# design.net
KiCad netlist of a schematic drawn in Altium Designer
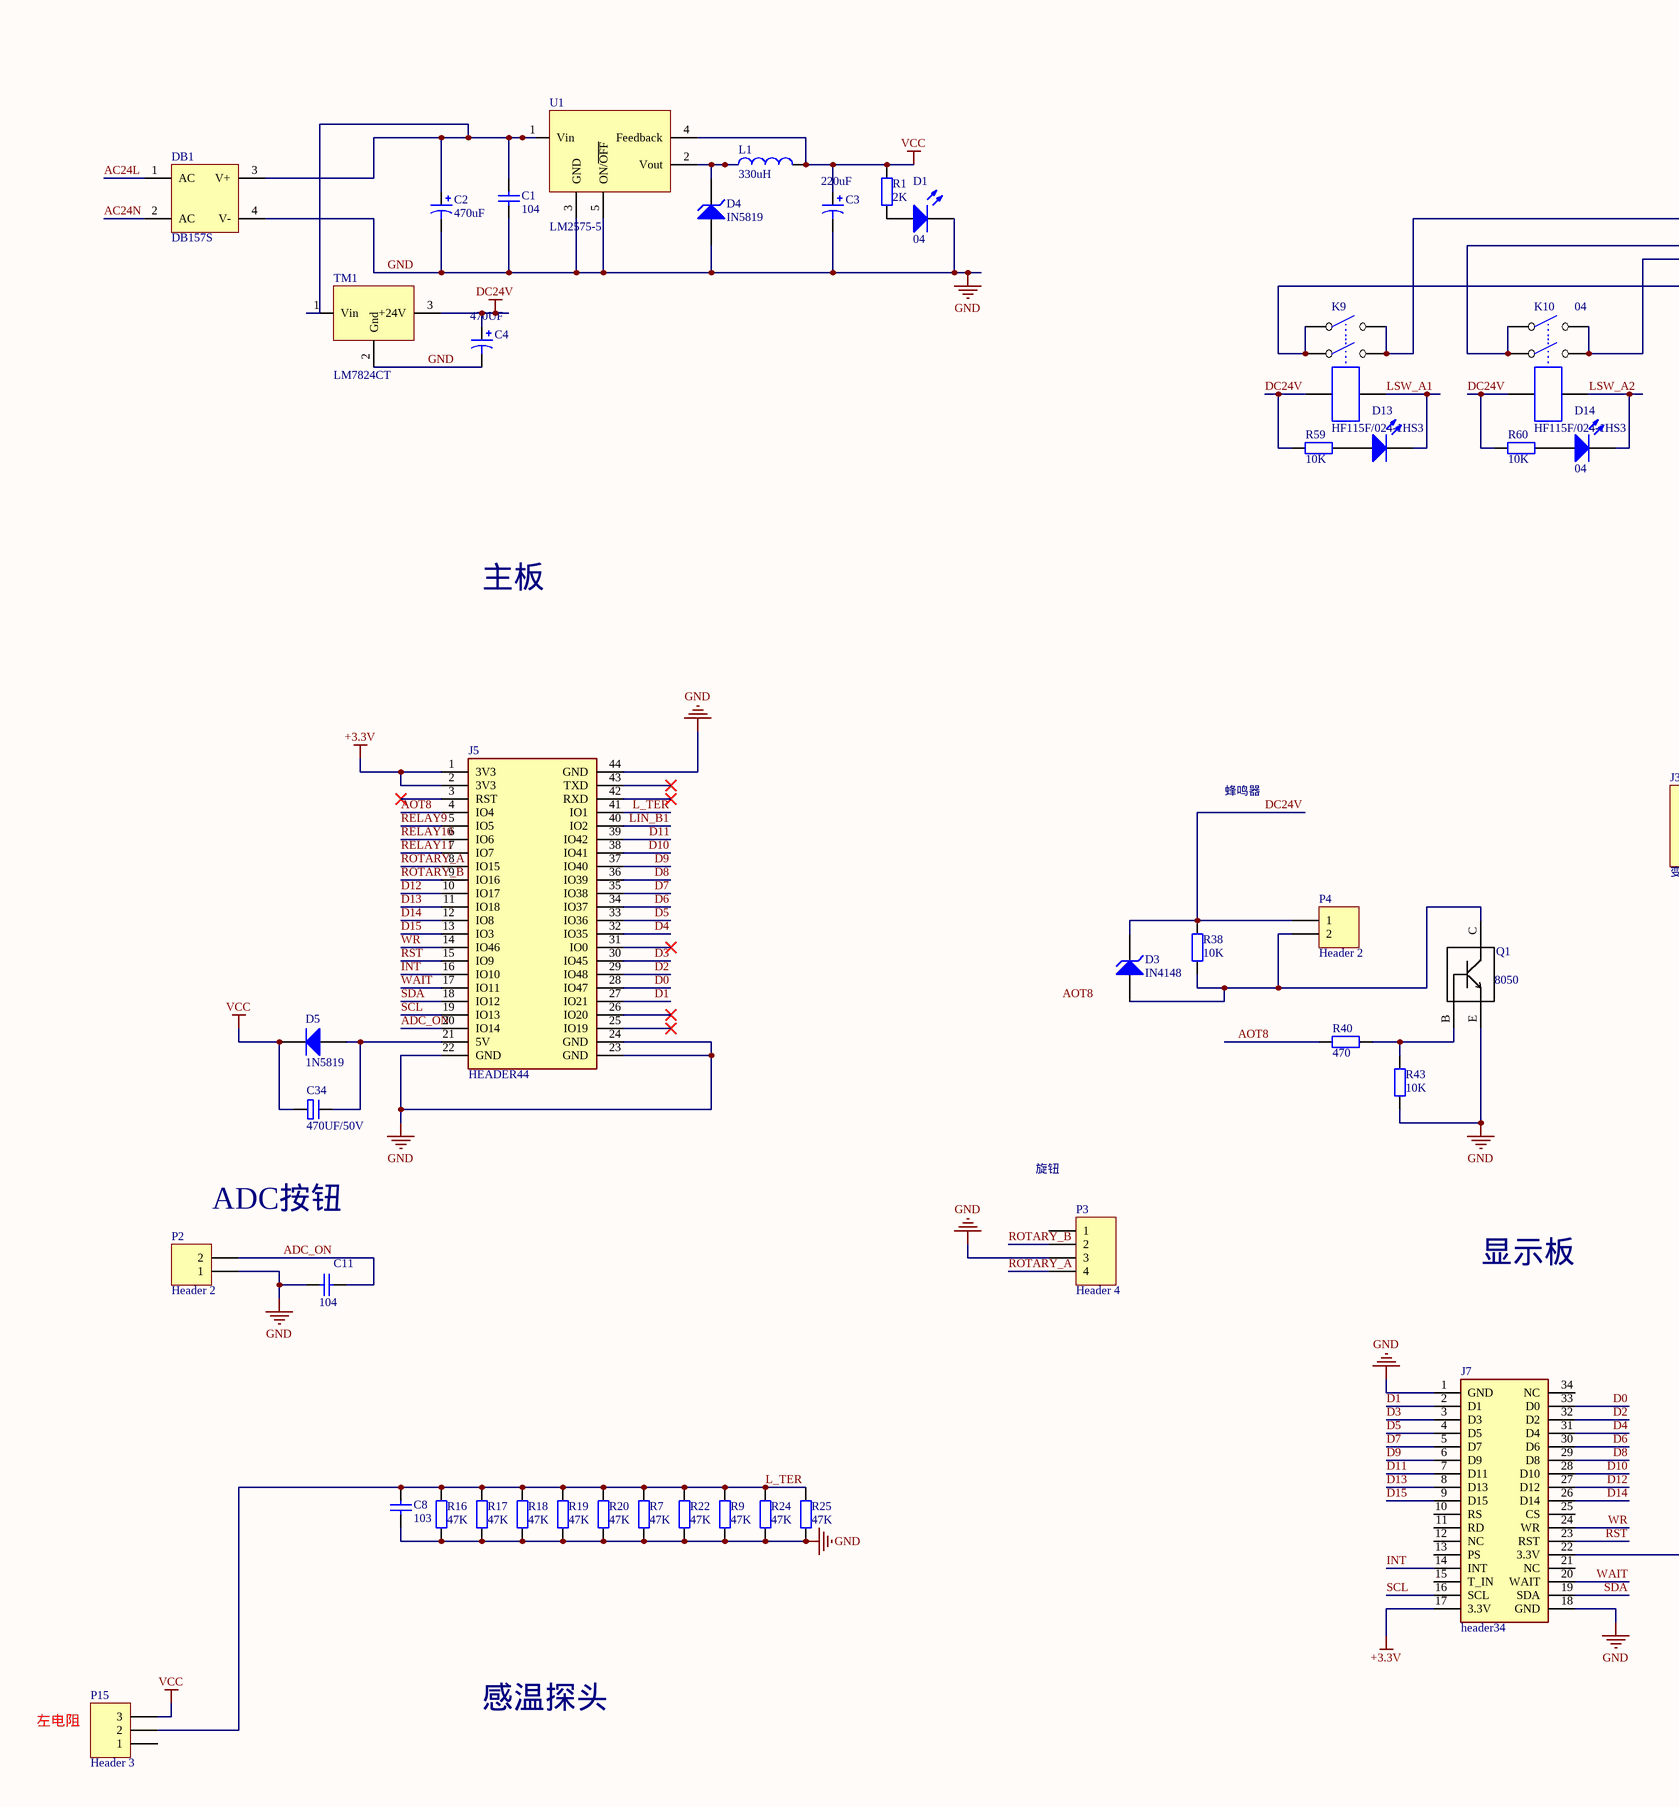
[diagram p0: 下程序新版.SchDoc, left]
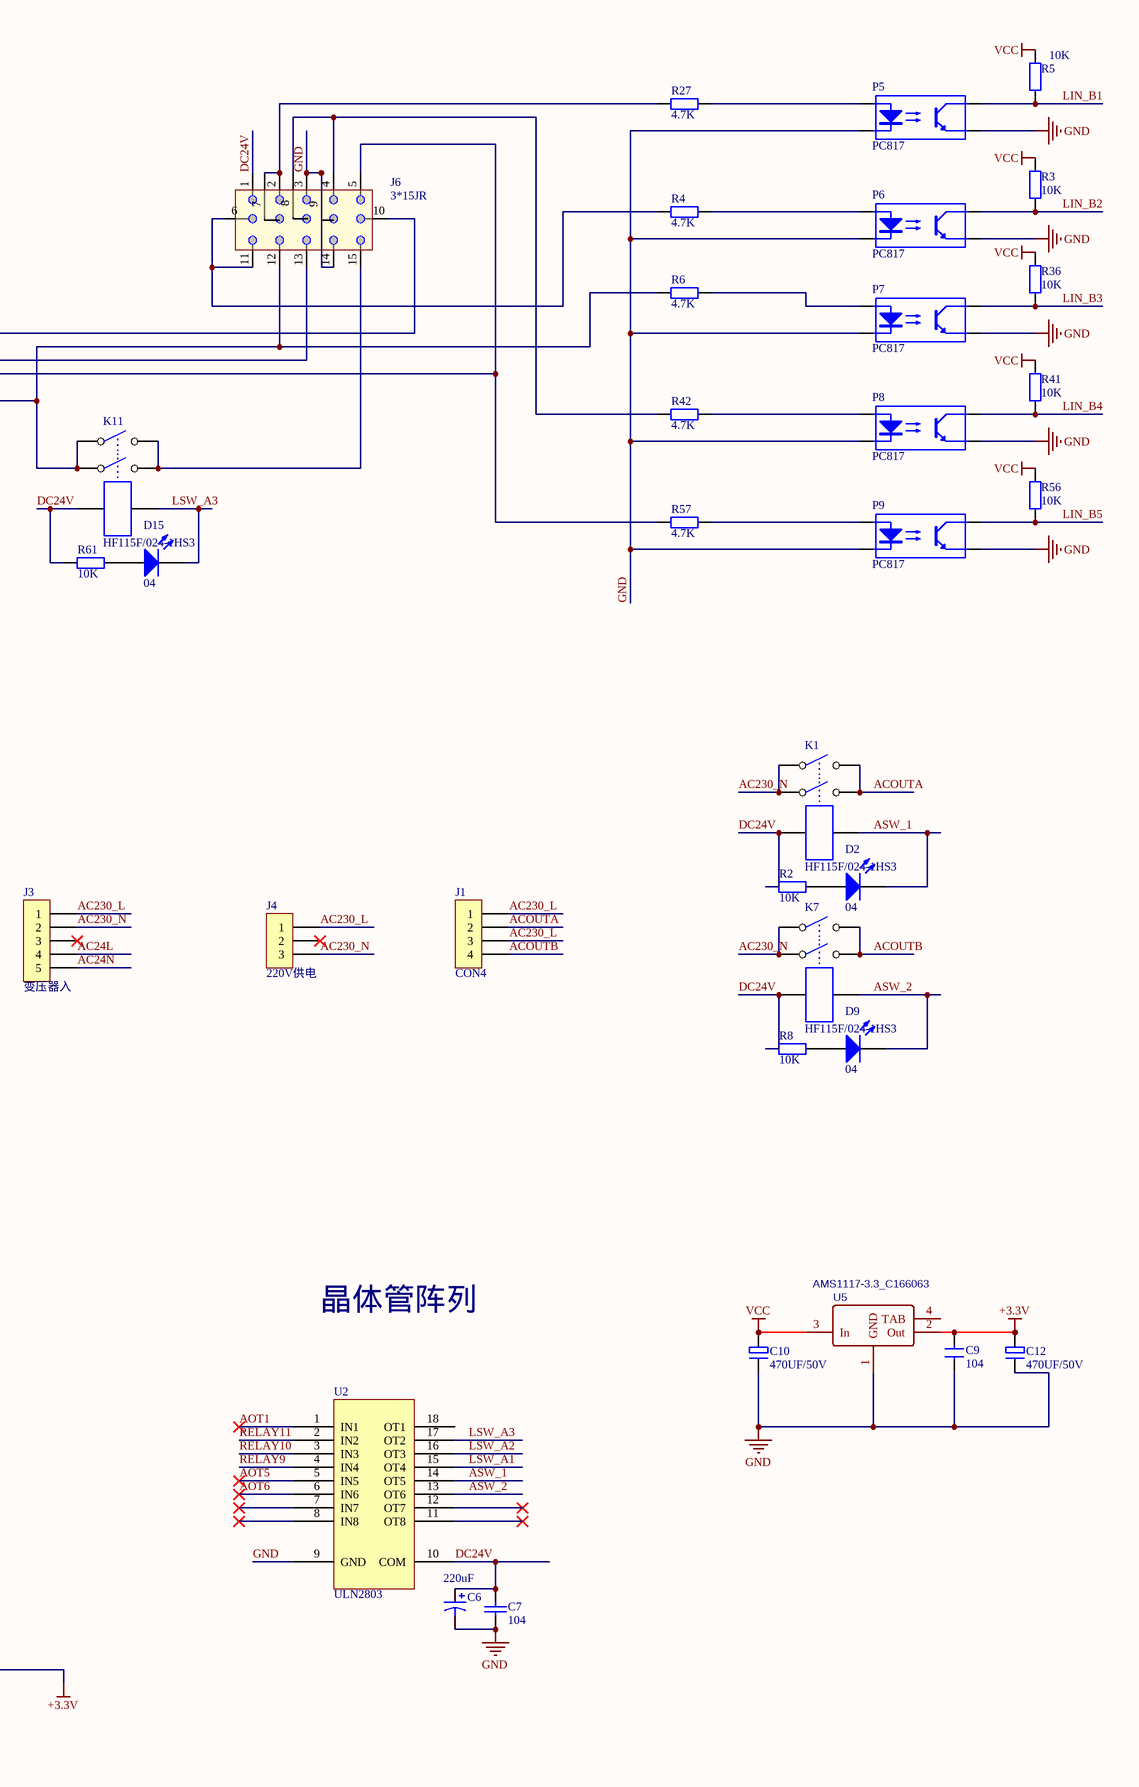
[diagram p1: 下程序新版.SchDoc, right]

(export (version "E")
  (design (tool "Eeschema 10.0.6"))
  (components
    (comp (ref "C1")
      (value "104")
      (footprint "PcbLib1:0805")
      (description "Capacitor")
      (fields (field (name "PUBLISHER") "Altium Limited"))
      (libsource (lib "Miscellaneous Devices") (part "Cap"))
    )
    (comp (ref "C2")
      (value "470uF")
      (footprint "PcbLib1:CD9")
      (description "Polarized Capacitor (Radial)")
      (fields (field (name "Comment") "470UF/50V") (field (name "PUBLISHER") "Altium Limited"))
      (libsource (lib "Miscellaneous Devices") (part "Cap Pol1"))
    )
    (comp (ref "C3")
      (value "220uF")
      (footprint "PcbLib1:CD9")
      (description "Polarized Capacitor (Radial)")
      (fields (field (name "PUBLISHER") "Altium Limited"))
      (libsource (lib "Miscellaneous Devices") (part "Cap Pol1"))
    )
    (comp (ref "C4")
      (value "470UF")
      (footprint "PcbLib1:CD9")
      (description "Polarized Capacitor (Radial)")
      (fields (field (name "PUBLISHER") "Altium Limited"))
      (libsource (lib "Miscellaneous Devices") (part "Cap Pol1"))
    )
    (comp (ref "C6")
      (value "220uF")
      (footprint "PcbLib1:CD9")
      (description "Polarized Capacitor (Radial)")
      (fields (field (name "PUBLISHER") "Altium Limited"))
      (libsource (lib "Miscellaneous Devices") (part "Cap Pol1"))
    )
    (comp (ref "C7")
      (value "104")
      (footprint "PcbLib1:0805")
      (description "Capacitor")
      (fields (field (name "PUBLISHER") "Altium Limited"))
      (libsource (lib "Miscellaneous Devices") (part "Cap"))
    )
    (comp (ref "C8")
      (value "103")
      (footprint "PcbLib1:0805")
      (description "Capacitor")
      (fields (field (name "PUBLISHER") "Altium Limited"))
      (libsource (lib "Miscellaneous Devices") (part "Cap"))
    )
    (comp (ref "C9") (value "104") (footprint "PcbLib1:0805") (libsource (lib "Altium") (part "CAP")))
    (comp (ref "C10") (value "470UF/50V") (footprint "PcbLib1:CD9") (libsource (lib "Altium") (part "ECAP")))
    (comp (ref "C11")
      (value "104")
      (footprint "PcbLib1:0805")
      (description "Capacitor")
      (fields (field (name "PUBLISHER") "Altium Limited"))
      (libsource (lib "Miscellaneous Devices") (part "Cap"))
    )
    (comp (ref "C12") (value "470UF/50V") (footprint "PcbLib1:CD9") (libsource (lib "Altium") (part "ECAP")))
    (comp (ref "C34") (value "470UF/50V") (footprint "PcbLib1:CD9") (libsource (lib "Altium") (part "ECAP")))
    (comp (ref "D1")
      (value "04")
      (footprint "PcbLib1:LED-T")
      (description "Typical INFRARED GaAs LED")
      (fields (field (name "PUBLISHER") "Altium Limited"))
      (libsource (lib "Miscellaneous Devices") (part "LED0"))
    )
    (comp (ref "D2")
      (value "04")
      (footprint "PcbLib1:LED-T")
      (description "Typical INFRARED GaAs LED")
      (fields (field (name "PUBLISHER") "Altium Limited"))
      (libsource (lib "Miscellaneous Devices") (part "LED0"))
    )
    (comp (ref "D3")
      (value "IN4148")
      (footprint "PcbLib1:DO-214AC")
      (description "Zener Diode")
      (fields (field (name "PUBLISHER") "Altium Limited"))
      (libsource (lib "Miscellaneous Devices") (part "D Zener"))
    )
    (comp (ref "D4")
      (value "IN5819")
      (footprint "PcbLib1:DO-214AC")
      (description "Zener Diode")
      (fields (field (name "PUBLISHER") "Altium Limited"))
      (libsource (lib "Miscellaneous Devices") (part "D Zener"))
    )
    (comp (ref "D5")
      (value "1N5819")
      (footprint "PcbLib1:DO-214AC")
      (description "High Conductance Fast Diode")
      (fields (field (name "PUBLISHER") "Altium Limited"))
      (libsource (lib "Drive") (part "Diode 1N4148"))
    )
    (comp (ref "D9")
      (value "04")
      (footprint "PcbLib1:LED-T")
      (description "Typical INFRARED GaAs LED")
      (fields (field (name "PUBLISHER") "Altium Limited"))
      (libsource (lib "Miscellaneous Devices") (part "LED0"))
    )
    (comp (ref "D13")
      (value "04")
      (footprint "PcbLib1:LED-T")
      (description "Typical INFRARED GaAs LED")
      (fields (field (name "PUBLISHER") "Altium Limited"))
      (libsource (lib "Miscellaneous Devices") (part "LED0"))
    )
    (comp (ref "D14")
      (value "04")
      (footprint "PcbLib1:LED-T")
      (description "Typical INFRARED GaAs LED")
      (fields (field (name "PUBLISHER") "Altium Limited"))
      (libsource (lib "Miscellaneous Devices") (part "LED0"))
    )
    (comp (ref "D15")
      (value "04")
      (footprint "PcbLib1:LED-T")
      (description "Typical INFRARED GaAs LED")
      (fields (field (name "PUBLISHER") "Altium Limited"))
      (libsource (lib "Miscellaneous Devices") (part "LED0"))
    )
    (comp (ref "DB1")
      (value "DB157S")
      (footprint "PcbLib1:LC-GBU")
      (libsource (lib "常用元件库") (part "BRIDGE2"))
    )
    (comp (ref "J1")
      (value "CON4")
      (footprint "PcbLib1:4PIN-6.3")
      (description "Connector")
      (libsource (lib "Miscellaneous Devices") (part "CON4"))
    )
    (comp (ref "J3")
      (value "变压器入")
      (footprint "PcbLib1:5PIN-6.3")
      (description "Connector")
      (libsource (lib "Miscellaneous Devices") (part "CON5"))
    )
    (comp (ref "J4")
      (value "220V供电")
      (footprint "PcbLib1:3PIN-6.3")
      (description "Connector")
      (libsource (lib "Miscellaneous Devices") (part "CON3"))
    )
    (comp (ref "J5")
      (value "HEADER44")
      (footprint "SAMTEC_HTSW-110-24-TM-D")
      (fields (field (name "MF") "Samtec") (field (name "MP") "HTSW11024TMD"))
      (libsource (lib "Drive") (part "HEADER44"))
    )
    (comp (ref "J6")
      (value "3*15JR")
      (footprint "PcbLib1:3*5PIN-6.3")
      (libsource (lib "Schlib1") (part "Component_1"))
    )
    (comp (ref "J7")
      (value "header34")
      (footprint "SAMTEC_HTSW-110-24-TM-D")
      (fields (field (name "MF") "Samtec") (field (name "MP") "HTSW11024TMD"))
      (libsource (lib "Drive") (part "header34"))
    )
    (comp (ref "K1")
      (value "HF115F/024-1HS3")
      (footprint "PcbLib1:HF115FA")
      (libsource (lib "Miscellaneous Devices") (part "RELAY-DPST"))
    )
    (comp (ref "K7")
      (value "HF115F/024-1HS3")
      (footprint "PcbLib1:HF115FA")
      (libsource (lib "Miscellaneous Devices") (part "RELAY-DPST"))
    )
    (comp (ref "K9")
      (value "HF115F/024-1HS3")
      (footprint "PcbLib1:HF115FA")
      (libsource (lib "Miscellaneous Devices") (part "RELAY-DPST"))
    )
    (comp (ref "K10")
      (value "HF115F/024-1HS3")
      (footprint "PcbLib1:HF115FA")
      (libsource (lib "Miscellaneous Devices") (part "RELAY-DPST"))
    )
    (comp (ref "K11")
      (value "HF115F/024-1HS3")
      (footprint "PcbLib1:HF115FA")
      (libsource (lib "Miscellaneous Devices") (part "RELAY-DPST"))
    )
    (comp (ref "L1")
      (value "330uH")
      (footprint "PcbLib1:SMD331")
      (description "Inductor")
      (fields (field (name "PUBLISHER") "Altium Limited"))
      (libsource (lib "Miscellaneous Devices") (part "Inductor"))
    )
    (comp (ref "P2")
      (value "Header 2")
      (footprint "PcbLib1:2PIN 3.96")
      (description "Header, 2-Pin")
      (fields (field (name "PUBLISHER") "Altium Limited"))
      (libsource (lib "Drive") (part "Header 2"))
    )
    (comp (ref "P3")
      (value "Header 4")
      (footprint "PcbLib1:4PIN 2.54")
      (description "Header, 4-Pin")
      (fields (field (name "PUBLISHER") "Altium Limited"))
      (libsource (lib "Drive") (part "Header 4"))
    )
    (comp (ref "P4")
      (value "Header 2")
      (footprint "PcbLib1:2PIN 3.96")
      (description "Header, 2-Pin")
      (fields (field (name "PUBLISHER") "Altium Limited"))
      (libsource (lib "Miscellaneous Connectors") (part "Header 2"))
    )
    (comp (ref "P5") (value "PC817") (footprint "PcbLib1:LC-SMD-4") (libsource (lib "常用元件库") (part "P521")))
    (comp (ref "P6") (value "PC817") (footprint "PcbLib1:LC-SMD-4") (libsource (lib "常用元件库") (part "P521")))
    (comp (ref "P7") (value "PC817") (footprint "PcbLib1:LC-SMD-4") (libsource (lib "常用元件库") (part "P521")))
    (comp (ref "P8") (value "PC817") (footprint "PcbLib1:LC-SMD-4") (libsource (lib "常用元件库") (part "P521")))
    (comp (ref "P9") (value "PC817") (footprint "PcbLib1:LC-SMD-4") (libsource (lib "常用元件库") (part "P521")))
    (comp (ref "P15")
      (value "Header 3")
      (footprint "PcbLib1:3PIN 3.96")
      (description "Header, 3-Pin")
      (fields (field (name "PUBLISHER") "Altium Limited"))
      (libsource (lib "Miscellaneous Connectors") (part "Header 3"))
    )
    (comp (ref "Q1")
      (value "8050")
      (footprint "PcbLib1:SOT-23 - duplicate")
      (libsource (lib "Schlib1") (part "BC817-8050"))
    )
    (comp (ref "R1")
      (value "2K")
      (footprint "PcbLib1:0805")
      (description "Resistor")
      (fields (field (name "PUBLISHER") "Altium Limited"))
      (libsource (lib "Miscellaneous Devices") (part "Res2"))
    )
    (comp (ref "R2")
      (value "10K")
      (footprint "PcbLib1:0805")
      (description "Resistor")
      (fields (field (name "Comment") "10k") (field (name "PUBLISHER") "Altium Limited"))
      (libsource (lib "") (part "Res2_2"))
    )
    (comp (ref "R3")
      (value "10K")
      (footprint "PcbLib1:0805")
      (description "Resistor")
      (fields (field (name "Comment") "10k") (field (name "PUBLISHER") "Altium Limited"))
      (libsource (lib "Miscellaneous Devices") (part "Res2"))
    )
    (comp (ref "R4")
      (value "4.7K")
      (footprint "PcbLib1:0805")
      (description "Resistor")
      (fields (field (name "PUBLISHER") "Altium Limited"))
      (libsource (lib "") (part "Res2_1"))
    )
    (comp (ref "R5")
      (value "10K")
      (footprint "PcbLib1:0805")
      (description "Resistor")
      (fields (field (name "Comment") "10k") (field (name "PUBLISHER") "Altium Limited"))
      (libsource (lib "Miscellaneous Devices") (part "Res2"))
    )
    (comp (ref "R6")
      (value "4.7K")
      (footprint "PcbLib1:0805")
      (description "Resistor")
      (fields (field (name "PUBLISHER") "Altium Limited"))
      (libsource (lib "") (part "Res2_1"))
    )
    (comp (ref "R7")
      (value "47K")
      (footprint "PcbLib1:0805")
      (description "Resistor")
      (fields (field (name "PUBLISHER") "Altium Limited"))
      (libsource (lib "Miscellaneous Devices") (part "Res2"))
    )
    (comp (ref "R8")
      (value "10K")
      (footprint "PcbLib1:0805")
      (description "Resistor")
      (fields (field (name "Comment") "10k") (field (name "PUBLISHER") "Altium Limited"))
      (libsource (lib "") (part "Res2_2"))
    )
    (comp (ref "R9")
      (value "47K")
      (footprint "PcbLib1:0805")
      (description "Resistor")
      (fields (field (name "PUBLISHER") "Altium Limited"))
      (libsource (lib "Miscellaneous Devices") (part "Res2"))
    )
    (comp (ref "R16")
      (value "47K")
      (footprint "PcbLib1:0805")
      (description "Resistor")
      (fields (field (name "PUBLISHER") "Altium Limited"))
      (libsource (lib "Miscellaneous Devices") (part "Res2"))
    )
    (comp (ref "R17")
      (value "47K")
      (footprint "PcbLib1:0805")
      (description "Resistor")
      (fields (field (name "PUBLISHER") "Altium Limited"))
      (libsource (lib "Miscellaneous Devices") (part "Res2"))
    )
    (comp (ref "R18")
      (value "47K")
      (footprint "PcbLib1:0805")
      (description "Resistor")
      (fields (field (name "PUBLISHER") "Altium Limited"))
      (libsource (lib "Miscellaneous Devices") (part "Res2"))
    )
    (comp (ref "R19")
      (value "47K")
      (footprint "PcbLib1:0805")
      (description "Resistor")
      (fields (field (name "PUBLISHER") "Altium Limited"))
      (libsource (lib "Miscellaneous Devices") (part "Res2"))
    )
    (comp (ref "R20")
      (value "47K")
      (footprint "PcbLib1:0805")
      (description "Resistor")
      (fields (field (name "PUBLISHER") "Altium Limited"))
      (libsource (lib "Miscellaneous Devices") (part "Res2"))
    )
    (comp (ref "R22")
      (value "47K")
      (footprint "PcbLib1:0805")
      (description "Resistor")
      (fields (field (name "PUBLISHER") "Altium Limited"))
      (libsource (lib "Miscellaneous Devices") (part "Res2"))
    )
    (comp (ref "R24")
      (value "47K")
      (footprint "PcbLib1:0805")
      (description "Resistor")
      (fields (field (name "PUBLISHER") "Altium Limited"))
      (libsource (lib "Miscellaneous Devices") (part "Res2"))
    )
    (comp (ref "R25")
      (value "47K")
      (footprint "PcbLib1:0805")
      (description "Resistor")
      (fields (field (name "PUBLISHER") "Altium Limited"))
      (libsource (lib "Miscellaneous Devices") (part "Res2"))
    )
    (comp (ref "R27")
      (value "4.7K")
      (footprint "PcbLib1:0805")
      (description "Resistor")
      (fields (field (name "PUBLISHER") "Altium Limited"))
      (libsource (lib "") (part "Res2_1"))
    )
    (comp (ref "R36")
      (value "10K")
      (footprint "PcbLib1:0805")
      (description "Resistor")
      (fields (field (name "Comment") "10k") (field (name "PUBLISHER") "Altium Limited"))
      (libsource (lib "Miscellaneous Devices") (part "Res2"))
    )
    (comp (ref "R38")
      (value "10K")
      (footprint "0805")
      (description "Resistor")
      (fields (field (name "PUBLISHER") "Altium Limited"))
      (libsource (lib "Miscellaneous Devices") (part "Res2"))
    )
    (comp (ref "R40")
      (value "470")
      (footprint "0805")
      (description "Resistor")
      (fields (field (name "PUBLISHER") "Altium Limited"))
      (libsource (lib "") (part "Res2_1"))
    )
    (comp (ref "R41")
      (value "10K")
      (footprint "PcbLib1:0805")
      (description "Resistor")
      (fields (field (name "Comment") "10k") (field (name "PUBLISHER") "Altium Limited"))
      (libsource (lib "Miscellaneous Devices") (part "Res2"))
    )
    (comp (ref "R42")
      (value "4.7K")
      (footprint "PcbLib1:0805")
      (description "Resistor")
      (fields (field (name "PUBLISHER") "Altium Limited"))
      (libsource (lib "") (part "Res2_1"))
    )
    (comp (ref "R43")
      (value "10K")
      (footprint "0805")
      (description "Resistor")
      (fields (field (name "PUBLISHER") "Altium Limited"))
      (libsource (lib "Miscellaneous Devices") (part "Res2"))
    )
    (comp (ref "R56")
      (value "10K")
      (footprint "PcbLib1:0805")
      (description "Resistor")
      (fields (field (name "Comment") "10k") (field (name "PUBLISHER") "Altium Limited"))
      (libsource (lib "Miscellaneous Devices") (part "Res2"))
    )
    (comp (ref "R57")
      (value "4.7K")
      (footprint "PcbLib1:0805")
      (description "Resistor")
      (fields (field (name "PUBLISHER") "Altium Limited"))
      (libsource (lib "") (part "Res2_1"))
    )
    (comp (ref "R59")
      (value "10K")
      (footprint "PcbLib1:0805")
      (description "Resistor")
      (fields (field (name "Comment") "10k") (field (name "PUBLISHER") "Altium Limited"))
      (libsource (lib "") (part "Res2_2"))
    )
    (comp (ref "R60")
      (value "10K")
      (footprint "PcbLib1:0805")
      (description "Resistor")
      (fields (field (name "Comment") "10k") (field (name "PUBLISHER") "Altium Limited"))
      (libsource (lib "") (part "Res2_2"))
    )
    (comp (ref "R61")
      (value "10K")
      (footprint "PcbLib1:0805")
      (description "Resistor")
      (fields (field (name "Comment") "10k") (field (name "PUBLISHER") "Altium Limited"))
      (libsource (lib "") (part "Res2_2"))
    )
    (comp (ref "TM1")
      (value "LM7824CT")
      (footprint "常用元件封装:TO-220")
      (libsource (lib "单片机及相关") (part "LM7824CT"))
    )
    (comp (ref "U1")
      (value "LM2575-5")
      (footprint "PcbLib1:D2PAK")
      (libsource (lib "ATmega169") (part "LM2575"))
    )
    (comp (ref "U2")
      (value "ULN2803")
      (footprint "PcbLib1:SOP-18_300mil")
      (libsource (lib "Schlib1") (part "ULN2803"))
    )
    (comp (ref "U5")
      (value "AMS1117-3.3_C166063")
      (footprint "PcbLib1:SOT-223_L6.7-W3.5-P2.30-BR")
      (fields
        (field (name "BOM_SUPPLIER PART") "C166063")
        (field (name "BOM_MANUFACTURER PART") "AMS1117-1.5")
        (field (name "CONTRIBUTOR") "LCSC")
      )
      (libsource (lib "Schlib1") (part "AMS1117-1.5_C166063"))
    )
  )
  (nets
    (net (code "1") (name "+3.3V") (class "Default")
      (node (ref "C12") (pin "1") (pinfunction "1_1") (pintype "passive"))
      (node (ref "C9") (pin "1") (pintype "passive"))
      (node (ref "J5") (pin "1") (pinfunction "3V3_1") (pintype "passive"))
      (node (ref "J5") (pin "2") (pinfunction "3V3_2") (pintype "passive"))
      (node (ref "J7") (pin "17") (pinfunction "3.3V_17") (pintype "passive"))
      (node (ref "J7") (pin "22") (pinfunction "3.3V_22") (pintype "passive"))
      (node (ref "U5") (pin "2") (pinfunction "Out_2") (pintype "passive"))
    )
    (net (code "2") (name "/AC24L") (class "Default")
      (node (ref "DB1") (pin "1") (pinfunction "AC_1") (pintype "passive"))
      (node (ref "J3") (pin "4") (pinfunction "4_4") (pintype "passive"))
    )
    (net (code "3") (name "/AC24N") (class "Default")
      (node (ref "DB1") (pin "2") (pinfunction "AC_2") (pintype "passive"))
      (node (ref "J3") (pin "5") (pinfunction "5_5") (pintype "passive"))
    )
    (net (code "4") (name "/AC230_L") (class "Default")
      (node (ref "J1") (pin "1") (pinfunction "1_1") (pintype "passive"))
      (node (ref "J1") (pin "3") (pinfunction "3_3") (pintype "passive"))
      (node (ref "J3") (pin "1") (pinfunction "1_1") (pintype "passive"))
      (node (ref "J4") (pin "1") (pinfunction "1_1") (pintype "passive"))
    )
    (net (code "5") (name "/AC230_N") (class "Default")
      (node (ref "J3") (pin "2") (pinfunction "2_2") (pintype "passive"))
      (node (ref "J4") (pin "3") (pinfunction "3_3") (pintype "passive"))
      (node (ref "K1") (pin "1") (pinfunction "1_1") (pintype "passive"))
      (node (ref "K1") (pin "3") (pinfunction "3_3") (pintype "passive"))
      (node (ref "K7") (pin "1") (pinfunction "1_1") (pintype "passive"))
      (node (ref "K7") (pin "3") (pinfunction "3_3") (pintype "passive"))
    )
    (net (code "6") (name "/ACOUTA") (class "Default")
      (node (ref "J1") (pin "2") (pinfunction "2_2") (pintype "passive"))
      (node (ref "K1") (pin "2") (pinfunction "2_2") (pintype "passive"))
      (node (ref "K1") (pin "4") (pinfunction "4_4") (pintype "passive"))
    )
    (net (code "7") (name "/ACOUTB") (class "Default")
      (node (ref "J1") (pin "4") (pinfunction "4_4") (pintype "passive"))
      (node (ref "K7") (pin "2") (pinfunction "2_2") (pintype "passive"))
      (node (ref "K7") (pin "4") (pinfunction "4_4") (pintype "passive"))
    )
    (net (code "8") (name "/ADC_ON") (class "Default")
      (node (ref "C11") (pin "1") (pinfunction "1_1") (pintype "passive"))
      (node (ref "J5") (pin "20") (pinfunction "IO14_20") (pintype "passive"))
      (node (ref "P2") (pin "2") (pinfunction "2_2") (pintype "passive"))
    )
    (net (code "9") (name "/AOT1") (class "Default")
      (node (ref "U2") (pin "1") (pinfunction "IN1_1") (pintype "passive+no_connect"))
    )
    (net (code "10") (name "/AOT5") (class "Default")
      (node (ref "U2") (pin "5") (pinfunction "IN5_5") (pintype "passive+no_connect"))
    )
    (net (code "11") (name "/AOT6") (class "Default")
      (node (ref "U2") (pin "6") (pinfunction "IN6_6") (pintype "passive+no_connect"))
    )
    (net (code "12") (name "/AOT8") (class "Default")
      (node (ref "J5") (pin "4") (pinfunction "IO4_4") (pintype "passive"))
      (node (ref "R40") (pin "1") (pinfunction "1_1") (pintype "passive"))
    )
    (net (code "13") (name "/ASW_1") (class "Default")
      (node (ref "D2") (pin "2") (pinfunction "K_2") (pintype "passive"))
      (node (ref "K1") (pin "6") (pinfunction "6_6") (pintype "passive"))
      (node (ref "U2") (pin "14") (pinfunction "OT5_14") (pintype "passive"))
    )
    (net (code "14") (name "/ASW_2") (class "Default")
      (node (ref "D9") (pin "2") (pinfunction "K_2") (pintype "passive"))
      (node (ref "K7") (pin "6") (pinfunction "6_6") (pintype "passive"))
      (node (ref "U2") (pin "13") (pinfunction "OT6_13") (pintype "passive"))
    )
    (net (code "15") (name "/D0") (class "Default")
      (node (ref "J5") (pin "28") (pinfunction "IO47_28") (pintype "passive"))
      (node (ref "J7") (pin "33") (pinfunction "D0_33") (pintype "passive"))
    )
    (net (code "16") (name "/D1") (class "Default")
      (node (ref "J5") (pin "27") (pinfunction "IO21_27") (pintype "passive"))
      (node (ref "J7") (pin "2") (pinfunction "D1_2") (pintype "passive"))
    )
    (net (code "17") (name "/D2") (class "Default")
      (node (ref "J5") (pin "29") (pinfunction "IO48_29") (pintype "passive"))
      (node (ref "J7") (pin "32") (pinfunction "D2_32") (pintype "passive"))
    )
    (net (code "18") (name "/D3") (class "Default")
      (node (ref "J5") (pin "30") (pinfunction "IO45_30") (pintype "passive"))
      (node (ref "J7") (pin "3") (pinfunction "D3_3") (pintype "passive"))
    )
    (net (code "19") (name "/D4") (class "Default")
      (node (ref "J5") (pin "32") (pinfunction "IO35_32") (pintype "passive"))
      (node (ref "J7") (pin "31") (pinfunction "D4_31") (pintype "passive"))
    )
    (net (code "20") (name "/D5") (class "Default")
      (node (ref "J5") (pin "33") (pinfunction "IO36_33") (pintype "passive"))
      (node (ref "J7") (pin "4") (pinfunction "D5_4") (pintype "passive"))
    )
    (net (code "21") (name "/D6") (class "Default")
      (node (ref "J5") (pin "34") (pinfunction "IO37_34") (pintype "passive"))
      (node (ref "J7") (pin "30") (pinfunction "D6_30") (pintype "passive"))
    )
    (net (code "22") (name "/D7") (class "Default")
      (node (ref "J5") (pin "35") (pinfunction "IO38_35") (pintype "passive"))
      (node (ref "J7") (pin "5") (pinfunction "D7_5") (pintype "passive"))
    )
    (net (code "23") (name "/D8") (class "Default")
      (node (ref "J5") (pin "36") (pinfunction "IO39_36") (pintype "passive"))
      (node (ref "J7") (pin "29") (pinfunction "D8_29") (pintype "passive"))
    )
    (net (code "24") (name "/D9") (class "Default")
      (node (ref "J5") (pin "37") (pinfunction "IO40_37") (pintype "passive"))
      (node (ref "J7") (pin "6") (pinfunction "D9_6") (pintype "passive"))
    )
    (net (code "25") (name "/D10") (class "Default")
      (node (ref "J5") (pin "38") (pinfunction "IO41_38") (pintype "passive"))
      (node (ref "J7") (pin "28") (pinfunction "D10_28") (pintype "passive"))
    )
    (net (code "26") (name "/D11") (class "Default")
      (node (ref "J5") (pin "39") (pinfunction "IO42_39") (pintype "passive"))
      (node (ref "J7") (pin "7") (pinfunction "D11_7") (pintype "passive"))
    )
    (net (code "27") (name "/D12") (class "Default")
      (node (ref "J5") (pin "10") (pinfunction "IO17_10") (pintype "passive"))
      (node (ref "J7") (pin "27") (pinfunction "D12_27") (pintype "passive"))
    )
    (net (code "28") (name "/D13") (class "Default")
      (node (ref "J5") (pin "11") (pinfunction "IO18_11") (pintype "passive"))
      (node (ref "J7") (pin "8") (pinfunction "D13_8") (pintype "passive"))
    )
    (net (code "29") (name "/D14") (class "Default")
      (node (ref "J5") (pin "12") (pinfunction "IO8_12") (pintype "passive"))
      (node (ref "J7") (pin "26") (pinfunction "D14_26") (pintype "passive"))
    )
    (net (code "30") (name "/D15") (class "Default")
      (node (ref "J5") (pin "13") (pinfunction "IO3_13") (pintype "passive"))
      (node (ref "J7") (pin "9") (pinfunction "D15_9") (pintype "passive"))
    )
    (net (code "31") (name "/INT") (class "Default")
      (node (ref "J5") (pin "16") (pinfunction "IO10_16") (pintype "passive"))
      (node (ref "J7") (pin "14") (pinfunction "INT_14") (pintype "passive"))
    )
    (net (code "32") (name "/LIN_B1") (class "Default")
      (node (ref "J5") (pin "40") (pinfunction "IO2_40") (pintype "passive"))
      (node (ref "P5") (pin "4") (pinfunction "Collector_4") (pintype "passive"))
      (node (ref "R5") (pin "1") (pinfunction "1_1") (pintype "passive"))
    )
    (net (code "33") (name "/LIN_B2") (class "Default")
      (node (ref "P6") (pin "4") (pinfunction "Collector_4") (pintype "passive"))
      (node (ref "R3") (pin "1") (pinfunction "1_1") (pintype "passive"))
    )
    (net (code "34") (name "/LIN_B3") (class "Default")
      (node (ref "P7") (pin "4") (pinfunction "Collector_4") (pintype "passive"))
      (node (ref "R36") (pin "1") (pinfunction "1_1") (pintype "passive"))
    )
    (net (code "35") (name "/LIN_B4") (class "Default")
      (node (ref "P8") (pin "4") (pinfunction "Collector_4") (pintype "passive"))
      (node (ref "R41") (pin "1") (pinfunction "1_1") (pintype "passive"))
    )
    (net (code "36") (name "/LIN_B5") (class "Default")
      (node (ref "P9") (pin "4") (pinfunction "Collector_4") (pintype "passive"))
      (node (ref "R56") (pin "1") (pinfunction "1_1") (pintype "passive"))
    )
    (net (code "37") (name "/LSW_A1") (class "Default")
      (node (ref "D13") (pin "2") (pinfunction "K_2") (pintype "passive"))
      (node (ref "K9") (pin "6") (pinfunction "6_6") (pintype "passive"))
      (node (ref "U2") (pin "15") (pinfunction "OT4_15") (pintype "passive"))
    )
    (net (code "38") (name "/LSW_A2") (class "Default")
      (node (ref "D14") (pin "2") (pinfunction "K_2") (pintype "passive"))
      (node (ref "K10") (pin "6") (pinfunction "6_6") (pintype "passive"))
      (node (ref "U2") (pin "16") (pinfunction "OT3_16") (pintype "power_in"))
    )
    (net (code "39") (name "/LSW_A3") (class "Default")
      (node (ref "D15") (pin "2") (pinfunction "K_2") (pintype "passive"))
      (node (ref "K11") (pin "6") (pinfunction "6_6") (pintype "passive"))
      (node (ref "U2") (pin "17") (pinfunction "OT2_17") (pintype "passive"))
    )
    (net (code "40") (name "/L_TER") (class "Default")
      (node (ref "C8") (pin "2") (pinfunction "2_2") (pintype "passive"))
      (node (ref "J5") (pin "41") (pinfunction "IO1_41") (pintype "passive"))
      (node (ref "P15") (pin "2") (pinfunction "2_2") (pintype "passive"))
      (node (ref "R16") (pin "2") (pinfunction "2_2") (pintype "passive"))
      (node (ref "R17") (pin "2") (pinfunction "2_2") (pintype "passive"))
      (node (ref "R18") (pin "2") (pinfunction "2_2") (pintype "passive"))
      (node (ref "R19") (pin "2") (pinfunction "2_2") (pintype "passive"))
      (node (ref "R20") (pin "2") (pinfunction "2_2") (pintype "passive"))
      (node (ref "R22") (pin "2") (pinfunction "2_2") (pintype "passive"))
      (node (ref "R24") (pin "2") (pinfunction "2_2") (pintype "passive"))
      (node (ref "R25") (pin "2") (pinfunction "2_2") (pintype "passive"))
      (node (ref "R7") (pin "2") (pinfunction "2_2") (pintype "passive"))
      (node (ref "R9") (pin "2") (pinfunction "2_2") (pintype "passive"))
    )
    (net (code "41") (name "/RELAY9") (class "Default")
      (node (ref "J5") (pin "5") (pinfunction "IO5_5") (pintype "passive"))
      (node (ref "U2") (pin "4") (pinfunction "IN4_4") (pintype "passive"))
    )
    (net (code "42") (name "/RELAY10") (class "Default")
      (node (ref "J5") (pin "6") (pinfunction "IO6_6") (pintype "passive"))
      (node (ref "U2") (pin "3") (pinfunction "IN3_3") (pintype "passive"))
    )
    (net (code "43") (name "/RELAY11") (class "Default")
      (node (ref "J5") (pin "7") (pinfunction "IO7_7") (pintype "passive"))
      (node (ref "U2") (pin "2") (pinfunction "IN2_2") (pintype "passive"))
    )
    (net (code "44") (name "/ROTARY_A") (class "Default")
      (node (ref "J5") (pin "8") (pinfunction "IO15_8") (pintype "passive"))
      (node (ref "P3") (pin "4") (pinfunction "4_4") (pintype "passive"))
    )
    (net (code "45") (name "/ROTARY_B") (class "Default")
      (node (ref "J5") (pin "9") (pinfunction "IO16_9") (pintype "passive"))
      (node (ref "P3") (pin "2") (pinfunction "2_2") (pintype "passive"))
    )
    (net (code "46") (name "/RST") (class "Default")
      (node (ref "J5") (pin "15") (pinfunction "IO9_15") (pintype "passive"))
      (node (ref "J7") (pin "23") (pinfunction "RST_23") (pintype "passive"))
    )
    (net (code "47") (name "/SCL") (class "Default")
      (node (ref "J5") (pin "19") (pinfunction "IO13_19") (pintype "passive"))
      (node (ref "J7") (pin "16") (pinfunction "SCL_16") (pintype "passive"))
    )
    (net (code "48") (name "/SDA") (class "Default")
      (node (ref "J5") (pin "18") (pinfunction "IO12_18") (pintype "passive"))
      (node (ref "J7") (pin "19") (pinfunction "SDA_19") (pintype "passive"))
    )
    (net (code "49") (name "/WAIT") (class "Default")
      (node (ref "J5") (pin "17") (pinfunction "IO11_17") (pintype "passive"))
      (node (ref "J7") (pin "20") (pinfunction "WAIT_20") (pintype "passive"))
    )
    (net (code "50") (name "/WR") (class "Default")
      (node (ref "J5") (pin "14") (pinfunction "IO46_14") (pintype "passive"))
      (node (ref "J7") (pin "24") (pinfunction "WR_24") (pintype "passive"))
    )
    (net (code "51") (name "DC24V") (class "Default")
      (node (ref "C4") (pin "1") (pinfunction "1_1") (pintype "passive"))
      (node (ref "C6") (pin "1") (pinfunction "1_1") (pintype "passive"))
      (node (ref "C7") (pin "2") (pinfunction "2_2") (pintype "passive"))
      (node (ref "D3") (pin "2") (pinfunction "K_2") (pintype "passive"))
      (node (ref "J6") (pin "1") (pinfunction "1_1") (pintype "passive"))
      (node (ref "K1") (pin "5") (pinfunction "5_5") (pintype "passive"))
      (node (ref "K10") (pin "5") (pinfunction "5_5") (pintype "passive"))
      (node (ref "K11") (pin "5") (pinfunction "5_5") (pintype "passive"))
      (node (ref "K7") (pin "5") (pinfunction "5_5") (pintype "passive"))
      (node (ref "K9") (pin "5") (pinfunction "5_5") (pintype "passive"))
      (node (ref "P4") (pin "1") (pinfunction "1_1") (pintype "passive"))
      (node (ref "R2") (pin "2") (pinfunction "2_2") (pintype "passive"))
      (node (ref "R38") (pin "2") (pinfunction "2_2") (pintype "passive"))
      (node (ref "R59") (pin "2") (pinfunction "2_2") (pintype "passive"))
      (node (ref "R60") (pin "2") (pinfunction "2_2") (pintype "passive"))
      (node (ref "R61") (pin "2") (pinfunction "2_2") (pintype "passive"))
      (node (ref "R8") (pin "2") (pinfunction "2_2") (pintype "passive"))
      (node (ref "TM1") (pin "3") (pinfunction "+24V_3") (pintype "passive"))
      (node (ref "U2") (pin "10") (pinfunction "COM_10") (pintype "passive"))
    )
    (net (code "52") (name "GND") (class "Default")
      (node (ref "C1") (pin "1") (pinfunction "1_1") (pintype "passive"))
      (node (ref "C10") (pin "2") (pinfunction "2_2") (pintype "passive"))
      (node (ref "C11") (pin "2") (pinfunction "2_2") (pintype "passive"))
      (node (ref "C12") (pin "2") (pinfunction "2_2") (pintype "passive"))
      (node (ref "C2") (pin "2") (pinfunction "2_2") (pintype "passive"))
      (node (ref "C3") (pin "2") (pinfunction "2_2") (pintype "passive"))
      (node (ref "C4") (pin "2") (pinfunction "2_2") (pintype "passive"))
      (node (ref "C6") (pin "2") (pinfunction "2_2") (pintype "passive"))
      (node (ref "C7") (pin "1") (pinfunction "1_1") (pintype "passive"))
      (node (ref "C8") (pin "1") (pinfunction "1_1") (pintype "passive"))
      (node (ref "C9") (pin "2") (pintype "passive"))
      (node (ref "D1") (pin "2") (pinfunction "K_2") (pintype "passive"))
      (node (ref "D4") (pin "1") (pinfunction "A_1") (pintype "passive"))
      (node (ref "DB1") (pin "4") (pinfunction "V-_4") (pintype "passive"))
      (node (ref "J5") (pin "22") (pinfunction "GND_22") (pintype "passive"))
      (node (ref "J5") (pin "23") (pinfunction "GND_23") (pintype "passive"))
      (node (ref "J5") (pin "24") (pinfunction "GND_24") (pintype "passive"))
      (node (ref "J5") (pin "44") (pinfunction "GND_44") (pintype "passive"))
      (node (ref "J6") (pin "14") (pinfunction "14_14") (pintype "passive"))
      (node (ref "J6") (pin "3") (pinfunction "3_3") (pintype "passive"))
      (node (ref "J6") (pin "9") (pinfunction "9_9") (pintype "passive"))
      (node (ref "J7") (pin "1") (pinfunction "GND_1") (pintype "passive"))
      (node (ref "J7") (pin "18") (pinfunction "GND_18") (pintype "passive"))
      (node (ref "P2") (pin "1") (pinfunction "1_1") (pintype "passive"))
      (node (ref "P3") (pin "3") (pinfunction "3_3") (pintype "passive"))
      (node (ref "P5") (pin "2") (pinfunction "LED_Cathode_2") (pintype "passive"))
      (node (ref "P5") (pin "3") (pinfunction "Emitter_3") (pintype "passive"))
      (node (ref "P6") (pin "2") (pinfunction "LED_Cathode_2") (pintype "passive"))
      (node (ref "P6") (pin "3") (pinfunction "Emitter_3") (pintype "passive"))
      (node (ref "P7") (pin "2") (pinfunction "LED_Cathode_2") (pintype "passive"))
      (node (ref "P7") (pin "3") (pinfunction "Emitter_3") (pintype "passive"))
      (node (ref "P8") (pin "2") (pinfunction "LED_Cathode_2") (pintype "passive"))
      (node (ref "P8") (pin "3") (pinfunction "Emitter_3") (pintype "passive"))
      (node (ref "P9") (pin "2") (pinfunction "LED_Cathode_2") (pintype "passive"))
      (node (ref "P9") (pin "3") (pinfunction "Emitter_3") (pintype "passive"))
      (node (ref "Q1") (pin "E") (pintype "passive"))
      (node (ref "R16") (pin "1") (pinfunction "1_1") (pintype "passive"))
      (node (ref "R17") (pin "1") (pinfunction "1_1") (pintype "passive"))
      (node (ref "R18") (pin "1") (pinfunction "1_1") (pintype "passive"))
      (node (ref "R19") (pin "1") (pinfunction "1_1") (pintype "passive"))
      (node (ref "R20") (pin "1") (pinfunction "1_1") (pintype "passive"))
      (node (ref "R22") (pin "1") (pinfunction "1_1") (pintype "passive"))
      (node (ref "R24") (pin "1") (pinfunction "1_1") (pintype "passive"))
      (node (ref "R25") (pin "1") (pinfunction "1_1") (pintype "passive"))
      (node (ref "R43") (pin "1") (pinfunction "1_1") (pintype "passive"))
      (node (ref "R7") (pin "1") (pinfunction "1_1") (pintype "passive"))
      (node (ref "R9") (pin "1") (pinfunction "1_1") (pintype "passive"))
      (node (ref "TM1") (pin "2") (pinfunction "Gnd_2") (pintype "passive"))
      (node (ref "U1") (pin "3") (pinfunction "GND_3") (pintype "passive"))
      (node (ref "U1") (pin "5") (pinfunction "ON/~{OFF}_5") (pintype "passive"))
      (node (ref "U2") (pin "9") (pinfunction "GND_9") (pintype "power_in"))
      (node (ref "U5") (pin "1") (pinfunction "GND_1") (pintype "passive"))
    )
    (net (code "53") (name "Net-(D1-A)") (class "Default")
      (node (ref "D1") (pin "1") (pinfunction "A_1") (pintype "passive"))
      (node (ref "R1") (pin "1") (pinfunction "1_1") (pintype "passive"))
    )
    (net (code "54") (name "Net-(D2-A)") (class "Default")
      (node (ref "D2") (pin "1") (pinfunction "A_1") (pintype "passive"))
      (node (ref "R2") (pin "1") (pinfunction "1_1") (pintype "passive"))
    )
    (net (code "55") (name "Net-(D3-A)") (class "Default")
      (node (ref "D3") (pin "1") (pinfunction "A_1") (pintype "passive"))
      (node (ref "P4") (pin "2") (pinfunction "2_2") (pintype "passive"))
      (node (ref "Q1") (pin "C") (pintype "passive"))
      (node (ref "R38") (pin "1") (pinfunction "1_1") (pintype "passive"))
    )
    (net (code "56") (name "Net-(D4-K)") (class "Default")
      (node (ref "D4") (pin "2") (pinfunction "K_2") (pintype "passive"))
      (node (ref "L1") (pin "1") (pinfunction "1_1") (pintype "passive"))
      (node (ref "U1") (pin "2") (pinfunction "Vout_2") (pintype "passive"))
    )
    (net (code "57") (name "Net-(D5-A)") (class "Default")
      (node (ref "C34") (pin "2") (pinfunction "2_2") (pintype "passive"))
      (node (ref "D5") (pin "1") (pinfunction "A_1") (pintype "passive"))
      (node (ref "J5") (pin "21") (pinfunction "5V_21") (pintype "passive"))
    )
    (net (code "58") (name "Net-(D9-A)") (class "Default")
      (node (ref "D9") (pin "1") (pinfunction "A_1") (pintype "passive"))
      (node (ref "R8") (pin "1") (pinfunction "1_1") (pintype "passive"))
    )
    (net (code "59") (name "Net-(D13-A)") (class "Default")
      (node (ref "D13") (pin "1") (pinfunction "A_1") (pintype "passive"))
      (node (ref "R59") (pin "1") (pinfunction "1_1") (pintype "passive"))
    )
    (net (code "60") (name "Net-(D14-A)") (class "Default")
      (node (ref "D14") (pin "1") (pinfunction "A_1") (pintype "passive"))
      (node (ref "R60") (pin "1") (pinfunction "1_1") (pintype "passive"))
    )
    (net (code "61") (name "Net-(D15-A)") (class "Default")
      (node (ref "D15") (pin "1") (pinfunction "A_1") (pintype "passive"))
      (node (ref "R61") (pin "1") (pinfunction "1_1") (pintype "passive"))
    )
    (net (code "62") (name "Net-(DB1-V+)") (class "Default")
      (node (ref "C1") (pin "2") (pinfunction "2_2") (pintype "passive"))
      (node (ref "C2") (pin "1") (pinfunction "1_1") (pintype "passive"))
      (node (ref "DB1") (pin "3") (pinfunction "V+_3") (pintype "passive"))
      (node (ref "TM1") (pin "1") (pinfunction "Vin_1") (pintype "passive"))
      (node (ref "U1") (pin "1") (pinfunction "Vin_1") (pintype "passive"))
    )
    (net (code "63") (name "Net-(J6-Pad2)") (class "Default")
      (node (ref "J6") (pin "2") (pinfunction "2_2") (pintype "passive"))
      (node (ref "J6") (pin "7") (pinfunction "7_7") (pintype "passive"))
      (node (ref "R27") (pin "1") (pinfunction "1_1") (pintype "passive"))
    )
    (net (code "64") (name "Net-(J6-Pad4)") (class "Default")
      (node (ref "J6") (pin "4") (pinfunction "4_4") (pintype "passive"))
      (node (ref "J6") (pin "8") (pinfunction "8_8") (pintype "passive"))
      (node (ref "R42") (pin "1") (pinfunction "1_1") (pintype "passive"))
    )
    (net (code "65") (name "Net-(J6-Pad5)") (class "Default")
      (node (ref "J6") (pin "5") (pinfunction "5_5") (pintype "passive"))
      (node (ref "K10") (pin "2") (pinfunction "2_2") (pintype "passive"))
      (node (ref "K10") (pin "4") (pinfunction "4_4") (pintype "passive"))
      (node (ref "R57") (pin "1") (pinfunction "1_1") (pintype "passive"))
    )
    (net (code "66") (name "Net-(J6-Pad10)") (class "Default")
      (node (ref "J6") (pin "10") (pinfunction "10_10") (pintype "passive"))
      (node (ref "K9") (pin "2") (pinfunction "2_2") (pintype "passive"))
      (node (ref "K9") (pin "4") (pinfunction "4_4") (pintype "passive"))
    )
    (net (code "67") (name "Net-(J6-Pad11)") (class "Default")
      (node (ref "J6") (pin "11") (pinfunction "11_11") (pintype "passive"))
      (node (ref "J6") (pin "6") (pinfunction "6_6") (pintype "passive"))
      (node (ref "R4") (pin "1") (pinfunction "1_1") (pintype "passive"))
    )
    (net (code "68") (name "Net-(J6-Pad12)") (class "Default")
      (node (ref "J6") (pin "12") (pinfunction "12_12") (pintype "passive"))
      (node (ref "K11") (pin "1") (pinfunction "1_1") (pintype "passive"))
      (node (ref "K11") (pin "3") (pinfunction "3_3") (pintype "passive"))
      (node (ref "K9") (pin "1") (pinfunction "1_1") (pintype "passive"))
      (node (ref "K9") (pin "3") (pinfunction "3_3") (pintype "passive"))
      (node (ref "R6") (pin "1") (pinfunction "1_1") (pintype "passive"))
    )
    (net (code "69") (name "Net-(J6-Pad13)") (class "Default")
      (node (ref "J6") (pin "13") (pinfunction "13_13") (pintype "passive"))
      (node (ref "K10") (pin "1") (pinfunction "1_1") (pintype "passive"))
      (node (ref "K10") (pin "3") (pinfunction "3_3") (pintype "passive"))
    )
    (net (code "70") (name "Net-(J6-Pad15)") (class "Default")
      (node (ref "J6") (pin "15") (pinfunction "15_15") (pintype "passive"))
      (node (ref "K11") (pin "2") (pinfunction "2_2") (pintype "passive"))
      (node (ref "K11") (pin "4") (pinfunction "4_4") (pintype "passive"))
    )
    (net (code "71") (name "Net-(P5-LED_Anode)") (class "Default")
      (node (ref "P5") (pin "1") (pinfunction "LED_Anode_1") (pintype "passive"))
      (node (ref "R27") (pin "2") (pinfunction "2_2") (pintype "passive"))
    )
    (net (code "72") (name "Net-(P6-LED_Anode)") (class "Default")
      (node (ref "P6") (pin "1") (pinfunction "LED_Anode_1") (pintype "passive"))
      (node (ref "R4") (pin "2") (pinfunction "2_2") (pintype "passive"))
    )
    (net (code "73") (name "Net-(P7-LED_Anode)") (class "Default")
      (node (ref "P7") (pin "1") (pinfunction "LED_Anode_1") (pintype "passive"))
      (node (ref "R6") (pin "2") (pinfunction "2_2") (pintype "passive"))
    )
    (net (code "74") (name "Net-(P8-LED_Anode)") (class "Default")
      (node (ref "P8") (pin "1") (pinfunction "LED_Anode_1") (pintype "passive"))
      (node (ref "R42") (pin "2") (pinfunction "2_2") (pintype "passive"))
    )
    (net (code "75") (name "Net-(P9-LED_Anode)") (class "Default")
      (node (ref "P9") (pin "1") (pinfunction "LED_Anode_1") (pintype "passive"))
      (node (ref "R57") (pin "2") (pinfunction "2_2") (pintype "passive"))
    )
    (net (code "76") (name "Net-(Q1-PadB)") (class "Default")
      (node (ref "Q1") (pin "B") (pintype "passive"))
      (node (ref "R40") (pin "2") (pinfunction "2_2") (pintype "passive"))
      (node (ref "R43") (pin "2") (pinfunction "2_2") (pintype "passive"))
    )
    (net (code "77") (name "VCC") (class "Default")
      (node (ref "C10") (pin "1") (pinfunction "1_1") (pintype "passive"))
      (node (ref "C3") (pin "1") (pinfunction "1_1") (pintype "passive"))
      (node (ref "C34") (pin "1") (pinfunction "1_1") (pintype "passive"))
      (node (ref "D5") (pin "2") (pinfunction "K_2") (pintype "passive"))
      (node (ref "L1") (pin "2") (pinfunction "2_2") (pintype "passive"))
      (node (ref "P15") (pin "3") (pinfunction "3_3") (pintype "passive"))
      (node (ref "R1") (pin "2") (pinfunction "2_2") (pintype "passive"))
      (node (ref "R3") (pin "2") (pinfunction "2_2") (pintype "passive"))
      (node (ref "R36") (pin "2") (pinfunction "2_2") (pintype "passive"))
      (node (ref "R41") (pin "2") (pinfunction "2_2") (pintype "passive"))
      (node (ref "R5") (pin "2") (pinfunction "2_2") (pintype "passive"))
      (node (ref "R56") (pin "2") (pinfunction "2_2") (pintype "passive"))
      (node (ref "U1") (pin "4") (pinfunction "Feedback_4") (pintype "passive"))
      (node (ref "U5") (pin "3") (pinfunction "In_3") (pintype "passive"))
    )
    (net (code "78") (name "unconnected-(J3-Pad3)") (class "Default")
      (node (ref "J3") (pin "3") (pinfunction "3_3") (pintype "passive+no_connect"))
    )
    (net (code "79") (name "unconnected-(J4-Pad2)") (class "Default")
      (node (ref "J4") (pin "2") (pinfunction "2_2") (pintype "passive+no_connect"))
    )
    (net (code "80") (name "unconnected-(J5-IO0-Pad31)") (class "Default")
      (node (ref "J5") (pin "31") (pinfunction "IO0_31") (pintype "passive+no_connect"))
    )
    (net (code "81") (name "unconnected-(J5-IO19-Pad25)") (class "Default")
      (node (ref "J5") (pin "25") (pinfunction "IO19_25") (pintype "passive+no_connect"))
    )
    (net (code "82") (name "unconnected-(J5-IO20-Pad26)") (class "Default")
      (node (ref "J5") (pin "26") (pinfunction "IO20_26") (pintype "passive+no_connect"))
    )
    (net (code "83") (name "unconnected-(J5-RST-Pad3)") (class "Default")
      (node (ref "J5") (pin "3") (pinfunction "RST_3") (pintype "passive+no_connect"))
    )
    (net (code "84") (name "unconnected-(J5-RXD-Pad42)") (class "Default")
      (node (ref "J5") (pin "42") (pinfunction "RXD_42") (pintype "passive+no_connect"))
    )
    (net (code "85") (name "unconnected-(J5-TXD-Pad43)") (class "Default")
      (node (ref "J5") (pin "43") (pinfunction "TXD_43") (pintype "passive+no_connect"))
    )
    (net (code "86") (name "unconnected-(J7-CS-Pad25)") (class "Default")
      (node (ref "J7") (pin "25") (pinfunction "CS_25") (pintype "passive"))
    )
    (net (code "87") (name "unconnected-(J7-NC-Pad12)") (class "Default")
      (node (ref "J7") (pin "12") (pinfunction "NC_12") (pintype "passive"))
    )
    (net (code "88") (name "unconnected-(J7-NC-Pad21)") (class "Default")
      (node (ref "J7") (pin "21") (pinfunction "NC_21") (pintype "passive"))
    )
    (net (code "89") (name "unconnected-(J7-NC-Pad34)") (class "Default")
      (node (ref "J7") (pin "34") (pinfunction "NC_34") (pintype "passive"))
    )
    (net (code "90") (name "unconnected-(J7-PS-Pad13)") (class "Default")
      (node (ref "J7") (pin "13") (pinfunction "PS_13") (pintype "passive"))
    )
    (net (code "91") (name "unconnected-(J7-RD-Pad11)") (class "Default")
      (node (ref "J7") (pin "11") (pinfunction "RD_11") (pintype "passive"))
    )
    (net (code "92") (name "unconnected-(J7-RS-Pad10)") (class "Default")
      (node (ref "J7") (pin "10") (pinfunction "RS_10") (pintype "passive"))
    )
    (net (code "93") (name "unconnected-(J7-T_IN-Pad15)") (class "Default")
      (node (ref "J7") (pin "15") (pinfunction "T_IN_15") (pintype "passive"))
    )
    (net (code "94") (name "unconnected-(P3-Pad1)") (class "Default")
      (node (ref "P3") (pin "1") (pinfunction "1_1") (pintype "passive"))
    )
    (net (code "95") (name "unconnected-(P15-Pad1)") (class "Default")
      (node (ref "P15") (pin "1") (pinfunction "1_1") (pintype "passive"))
    )
    (net (code "96") (name "unconnected-(U2-IN7-Pad7)") (class "Default")
      (node (ref "U2") (pin "7") (pinfunction "IN7_7") (pintype "passive+no_connect"))
    )
    (net (code "97") (name "unconnected-(U2-IN8-Pad8)") (class "Default")
      (node (ref "U2") (pin "8") (pinfunction "IN8_8") (pintype "passive+no_connect"))
    )
    (net (code "98") (name "unconnected-(U2-OT1-Pad18)") (class "Default")
      (node (ref "U2") (pin "18") (pinfunction "OT1_18") (pintype "passive"))
    )
    (net (code "99") (name "unconnected-(U2-OT7-Pad12)") (class "Default")
      (node (ref "U2") (pin "12") (pinfunction "OT7_12") (pintype "passive+no_connect"))
    )
    (net (code "100") (name "unconnected-(U2-OT8-Pad11)") (class "Default")
      (node (ref "U2") (pin "11") (pinfunction "OT8_11") (pintype "passive+no_connect"))
    )
    (net (code "101") (name "unconnected-(U5-TAB-Pad4)") (class "Default")
      (node (ref "U5") (pin "4") (pinfunction "TAB_4") (pintype "passive"))
    )
  )
)
